# DS153-1_0-B.net
KiCad netlist of a schematic drawn in Altium Designer
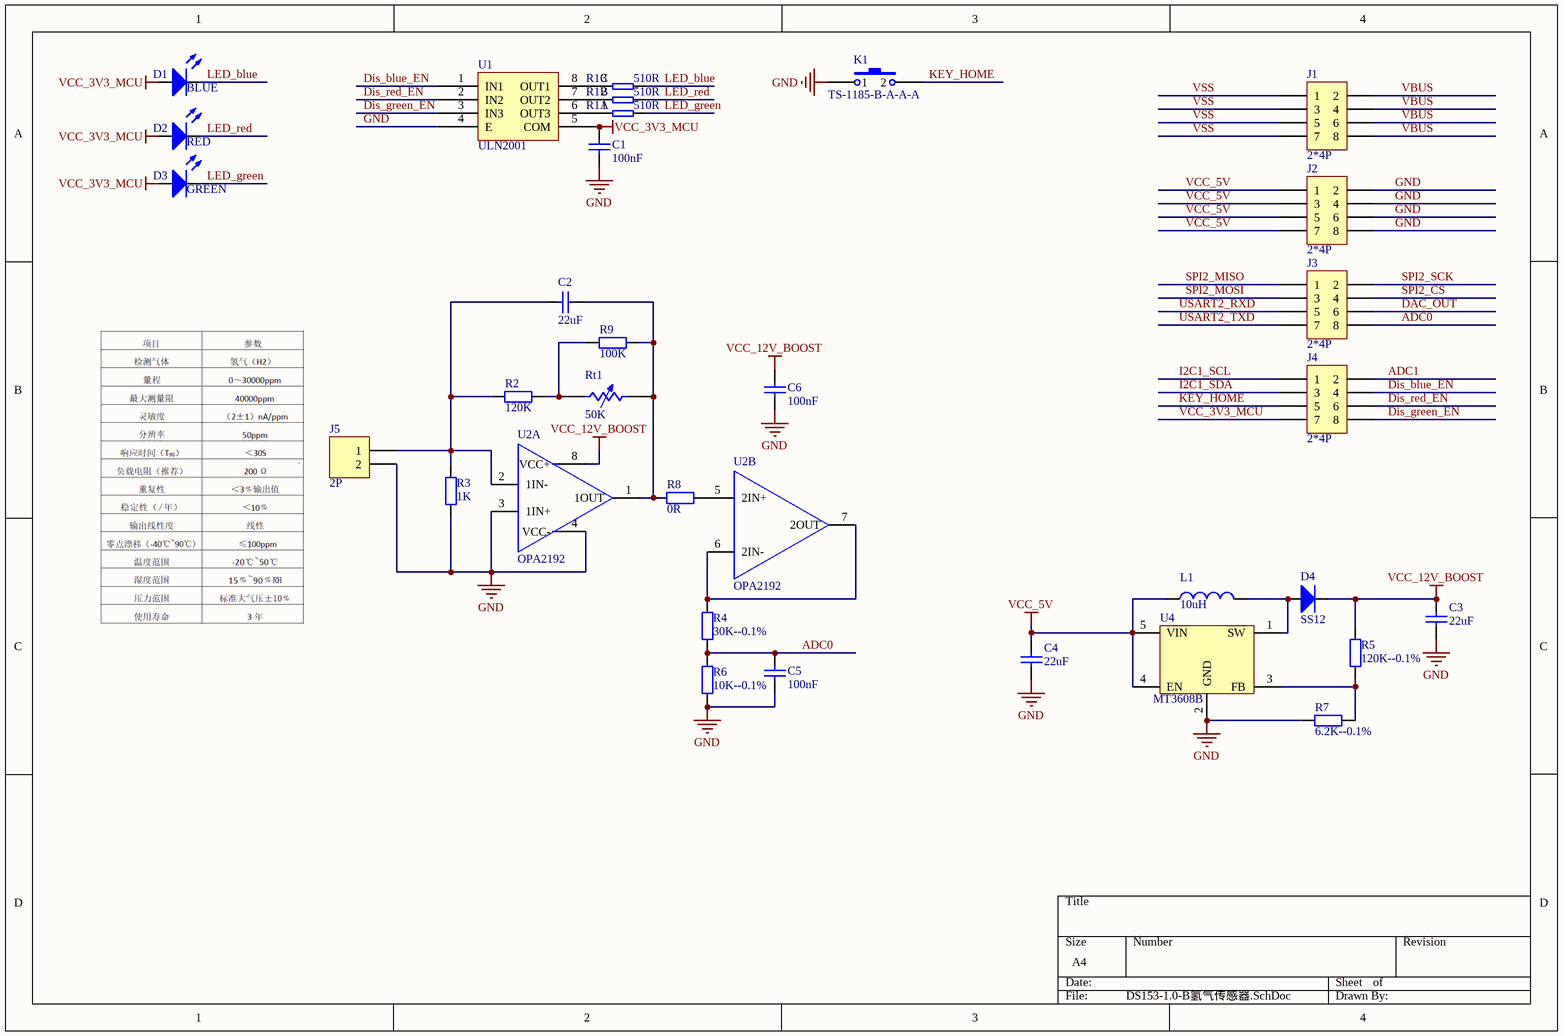
[diagram p0: DS153-1.0-B氢气传感器.SchDoc]

(export (version "E")
  (design (tool "Eeschema 10.0.6"))
  (components
    (comp (ref "C1")
      (value "100nF")
      (footprint "0603CAP")
      (description "贴片电容")
      (fields (field (name "Comment") "SMDCAP00013"))
      (libsource (lib "AD_SCH") (part "MLCC 100nF 50V ±10％ 0603"))
    )
    (comp (ref "C2")
      (value "22uF")
      (footprint "1206CAP")
      (description "贴片电容")
      (fields (field (name "Comment") "MLCC 22uF 50V ±20％ 1206"))
      (libsource (lib "AD_SCH") (part "MLCC 22uF 50V ±20％ 1206"))
    )
    (comp (ref "C3")
      (value "22uF")
      (footprint "1206CAP")
      (description "贴片电容")
      (fields (field (name "Comment") "MLCC 22uF 50V ±20％ 1206"))
      (libsource (lib "AD_SCH") (part "MLCC 22uF 50V ±20％ 1206"))
    )
    (comp (ref "C4")
      (value "22uF")
      (footprint "1206CAP")
      (description "贴片电容")
      (fields (field (name "Comment") "MLCC 22uF 50V ±20％ 1206"))
      (libsource (lib "AD_SCH") (part "MLCC 22uF 50V ±20％ 1206"))
    )
    (comp (ref "C5")
      (value "100nF")
      (footprint "0603CAP")
      (description "贴片电容")
      (fields (field (name "Comment") "SMDCAP00013"))
      (libsource (lib "AD_SCH") (part "MLCC 100nF 50V ±10％ 0603"))
    )
    (comp (ref "C6")
      (value "100nF")
      (footprint "0603CAP")
      (description "贴片电容")
      (fields (field (name "Comment") "SMDCAP00013"))
      (libsource (lib "AD_SCH") (part "MLCC 100nF 50V ±10％ 0603"))
    )
    (comp (ref "D1")
      (value "BLUE")
      (footprint "LED_0805")
      (description "贴片LED")
      (fields (field (name "Comment") "SMDLED00010"))
      (libsource (lib "AD_SCH") (part "Chip 蓝色LED 0805"))
    )
    (comp (ref "D2")
      (value "RED")
      (footprint "LED_0805")
      (description "贴片LED")
      (fields (field (name "Comment") "SMDLED00003"))
      (libsource (lib "AD_SCH") (part "Chip 红色LED 0805"))
    )
    (comp (ref "D3")
      (value "GREEN")
      (footprint "LED_0805")
      (description "贴片LED")
      (fields (field (name "Comment") "Chip 翠绿LED 0805"))
      (libsource (lib "AD_SCH") (part "Chip 翠绿LED 0805"))
    )
    (comp (ref "D4")
      (value "SS12")
      (footprint "SMA/DO-214AC")
      (description "贴片肖特基二极管")
      (fields (field (name "Comment") "SMDDIODE06003"))
      (libsource (lib "AD_SCH") (part "SS12 SMA/DO-214AC（1N5817）"))
    )
    (comp (ref "J1")
      (value "2*4P")
      (footprint "X1321WVS-2x04J-C40D53")
      (description "双排针2x4P 立贴 1.27mm")
      (fields (field (name "Comment") "X1321WVS-2x04J-C40D53"))
      (libsource (lib "AD_SCH") (part "X1321WVS-2x04J-C40D53"))
    )
    (comp (ref "J2")
      (value "2*4P")
      (footprint "X1321WVS-2x04J-C40D53")
      (description "双排针2x4P 立贴 1.27mm")
      (fields (field (name "Comment") "X1321WVS-2x04J-C40D53"))
      (libsource (lib "AD_SCH") (part "X1321WVS-2x04J-C40D53"))
    )
    (comp (ref "J3")
      (value "2*4P")
      (footprint "X1321WVS-2x04J-C40D53")
      (description "双排针2x4P 立贴 1.27mm")
      (fields (field (name "Comment") "X1321WVS-2x04J-C40D53"))
      (libsource (lib "AD_SCH") (part "X1321WVS-2x04J-C40D53"))
    )
    (comp (ref "J4")
      (value "2*4P")
      (footprint "X1321WVS-2x04J-C40D53")
      (description "双排针2x4P 立贴 1.27mm")
      (fields (field (name "Comment") "X1321WVS-2x04J-C40D53"))
      (libsource (lib "AD_SCH") (part "X1321WVS-2x04J-C40D53"))
    )
    (comp (ref "J5")
      (value "2P")
      (footprint "SIP2")
      (description "单排直针")
      (fields (field (name "Comment") "SL000000042"))
      (libsource (lib "AD_SCH") (part "DIP2 单排直针 1*40P 间距2.54mm 针长11mm 铜"))
    )
    (comp (ref "K1")
      (value "TS-1185-B-A-A-A")
      (footprint "KEY_TS-1185-x-A-A-A")
      (description "轻触开关")
      (libsource (lib "AD_SCH") (part "TS-1185-B-A-A-A"))
    )
    (comp (ref "L1")
      (value "小型化一体成型T-CORE,SMD,2x2.5mm")
      (footprint "SMD,2x2.5mm")
      (description "电感值 10uH ±20%\r\n饱和电流(Isat) 1.6A\r\n额定电流 1.2A\r\n直流电阻(DCR) 330mΩ")
      (libsource (lib "AD_SCH") (part "FTC252012S100MBCA"))
    )
    (comp (ref "R1")
      (value "510R")
      (footprint "0603RES_Pack4")
      (description "贴片排阻")
      (fields (field (name "Comment") "SMDRES05003"))
      (libsource (lib "AD_SCH") (part "Chip R*4 510R 1/16W ±5％ 0603"))
    )
    (comp (ref "R2")
      (value "120K")
      (footprint "0603RES")
      (description "贴片电阻")
      (fields (field (name "Comment") "Chip 120K 1/16W ±1％ 0603"))
      (libsource (lib "AD_SCH") (part "Chip 120K 1/16W ±1％ 0603"))
    )
    (comp (ref "R3")
      (value "1K")
      (footprint "0603RES")
      (description "贴片电阻")
      (fields (field (name "Comment") "SMDRES00034"))
      (libsource (lib "AD_SCH") (part "Chip 1K 1/16W ±1％ 0603"))
    )
    (comp (ref "R4")
      (value "30K--0.1%")
      (footprint "0603RES")
      (description "贴片电阻")
      (fields (field (name "Comment") "SMDRES00060"))
      (libsource (lib "AD_SCH") (part "Chip 30K 1/16W ±1％ 0603"))
    )
    (comp (ref "R5")
      (value "120K--0.1%")
      (footprint "0603RES")
      (description "贴片电阻")
      (fields (field (name "Comment") "Chip 120K 1/16W ±1％ 0603"))
      (libsource (lib "") (part "Chip 120K 1/16W ±1％ 0603_1"))
    )
    (comp (ref "R6")
      (value "10K--0.1%")
      (footprint "0603RES")
      (description "贴片电阻")
      (fields (field (name "Comment") "SMDRES00056"))
      (libsource (lib "AD_SCH") (part "Chip 10K 1/16W ±1％ 0603"))
    )
    (comp (ref "R7")
      (value "6.2K--0.1%")
      (footprint "0603RES")
      (description "贴片电阻")
      (fields (field (name "Comment") "SMDRES00056"))
      (libsource (lib "") (part "Chip 10K 1/16W ±1％ 0603_1"))
    )
    (comp (ref "R8")
      (value "0R")
      (footprint "0603RES")
      (description "贴片电阻")
      (fields (field (name "Comment") "Chip 0R 1/16W ±1％ 0603"))
      (libsource (lib "AD_SCH") (part "Chip 0R 1/16W ±1％ 0603"))
    )
    (comp (ref "R9")
      (value "100K")
      (footprint "0603RES")
      (description "贴片电阻")
      (fields (field (name "Comment") "SMDRES00071"))
      (libsource (lib "AD_SCH") (part "Chip 100K 1/16W ±1％ 0603"))
    )
    (comp (ref "Rt1")
      (value "50K")
      (footprint "DIP_CAP_2.54mm")
      (description "热敏电阻")
      (fields (field (name "Comment") "SE000000015"))
      (libsource (lib "AD_SCH") (part "NTC 10K 热敏电阻 5% Φ5 MF52A1 B值{colon}3950K"))
    )
    (comp (ref "U1")
      (value "ULN2001")
      (footprint "SO-8")
      (description "电机驱动芯片")
      (fields (field (name "Comment") "SMDIC000018"))
      (libsource (lib "AD_SCH") (part "ULN2001 SOP-8"))
    )
    (comp (ref "U2") (value "OPA2192") (footprint "SO-8") (libsource (lib "AD_SCH") (part "TL062C")))
    (comp (ref "U4")
      (value "MT3608B")
      (footprint "SOT23-6")
      (description "MT3608B 是一款高效的1.2MHz固定频率电流模式升压转换器。")
      (libsource (lib "AD_SCH") (part "MT3608B"))
    )
  )
  (nets
    (net (code "1") (name "/ADC0") (class "Default")
      (node (ref "C5") (pin "2") (pinfunction "2_2") (pintype "passive"))
      (node (ref "J3") (pin "8") (pinfunction "8_8") (pintype "passive"))
      (node (ref "R4") (pin "1") (pinfunction "1_1") (pintype "passive"))
      (node (ref "R6") (pin "2") (pinfunction "2_2") (pintype "passive"))
    )
    (net (code "2") (name "/ADC1") (class "Default")
      (node (ref "J4") (pin "2") (pinfunction "2_2") (pintype "passive"))
    )
    (net (code "3") (name "/DAC_OUT") (class "Default")
      (node (ref "J3") (pin "6") (pinfunction "6_6") (pintype "passive"))
    )
    (net (code "4") (name "/Dis_blue_EN") (class "Default")
      (node (ref "J4") (pin "4") (pinfunction "4_4") (pintype "passive"))
      (node (ref "U1") (pin "1") (pinfunction "IN1_1") (pintype "passive"))
    )
    (net (code "5") (name "/Dis_green_EN") (class "Default")
      (node (ref "J4") (pin "8") (pinfunction "8_8") (pintype "passive"))
      (node (ref "U1") (pin "3") (pinfunction "IN3_3") (pintype "passive"))
    )
    (net (code "6") (name "/Dis_red_EN") (class "Default")
      (node (ref "J4") (pin "6") (pinfunction "6_6") (pintype "passive"))
      (node (ref "U1") (pin "2") (pinfunction "IN2_2") (pintype "passive"))
    )
    (net (code "7") (name "/I2C1_SCL") (class "Default")
      (node (ref "J4") (pin "1") (pinfunction "1_1") (pintype "passive"))
    )
    (net (code "8") (name "/I2C1_SDA") (class "Default")
      (node (ref "J4") (pin "3") (pinfunction "3_3") (pintype "passive"))
    )
    (net (code "9") (name "/KEY_HOME") (class "Default")
      (node (ref "J4") (pin "5") (pinfunction "5_5") (pintype "passive"))
      (node (ref "K1") (pin "2") (pinfunction "2_2") (pintype "passive"))
    )
    (net (code "10") (name "/LED_blue") (class "Default")
      (node (ref "D1") (pin "2") (pinfunction "K_2") (pintype "passive"))
      (node (ref "R1") (pin "6") (pinfunction "6_6") (pintype "passive"))
    )
    (net (code "11") (name "/LED_green") (class "Default")
      (node (ref "D3") (pin "2") (pinfunction "K_2") (pintype "passive"))
      (node (ref "R1") (pin "8") (pinfunction "8_8") (pintype "passive"))
    )
    (net (code "12") (name "/LED_red") (class "Default")
      (node (ref "D2") (pin "2") (pinfunction "K_2") (pintype "passive"))
      (node (ref "R1") (pin "7") (pinfunction "7_7") (pintype "passive"))
    )
    (net (code "13") (name "/SPI2_CS") (class "Default")
      (node (ref "J3") (pin "4") (pinfunction "4_4") (pintype "passive"))
    )
    (net (code "14") (name "/SPI2_MISO") (class "Default")
      (node (ref "J3") (pin "1") (pinfunction "1_1") (pintype "passive"))
    )
    (net (code "15") (name "/SPI2_MOSI") (class "Default")
      (node (ref "J3") (pin "3") (pinfunction "3_3") (pintype "passive"))
    )
    (net (code "16") (name "/SPI2_SCK") (class "Default")
      (node (ref "J3") (pin "2") (pinfunction "2_2") (pintype "passive"))
    )
    (net (code "17") (name "/USART2_RXD") (class "Default")
      (node (ref "J3") (pin "5") (pinfunction "5_5") (pintype "passive"))
    )
    (net (code "18") (name "/USART2_TXD") (class "Default")
      (node (ref "J3") (pin "7") (pinfunction "7_7") (pintype "passive"))
    )
    (net (code "19") (name "/VBUS") (class "Default")
      (node (ref "J1") (pin "2") (pinfunction "2_2") (pintype "passive"))
      (node (ref "J1") (pin "4") (pinfunction "4_4") (pintype "passive"))
      (node (ref "J1") (pin "6") (pinfunction "6_6") (pintype "passive"))
      (node (ref "J1") (pin "8") (pinfunction "8_8") (pintype "passive"))
    )
    (net (code "20") (name "/VSS") (class "Default")
      (node (ref "J1") (pin "1") (pinfunction "1_1") (pintype "passive"))
      (node (ref "J1") (pin "3") (pinfunction "3_3") (pintype "passive"))
      (node (ref "J1") (pin "5") (pinfunction "5_5") (pintype "passive"))
      (node (ref "J1") (pin "7") (pinfunction "7_7") (pintype "passive"))
    )
    (net (code "21") (name "GND") (class "Default")
      (node (ref "C1") (pin "1") (pinfunction "1_1") (pintype "passive"))
      (node (ref "C3") (pin "2") (pinfunction "2_2") (pintype "passive"))
      (node (ref "C4") (pin "2") (pinfunction "2_2") (pintype "passive"))
      (node (ref "C5") (pin "1") (pinfunction "1_1") (pintype "passive"))
      (node (ref "C6") (pin "1") (pinfunction "1_1") (pintype "passive"))
      (node (ref "J2") (pin "2") (pinfunction "2_2") (pintype "passive"))
      (node (ref "J2") (pin "4") (pinfunction "4_4") (pintype "passive"))
      (node (ref "J2") (pin "6") (pinfunction "6_6") (pintype "passive"))
      (node (ref "J2") (pin "8") (pinfunction "8_8") (pintype "passive"))
      (node (ref "J5") (pin "2") (pinfunction "2_2") (pintype "passive"))
      (node (ref "K1") (pin "1") (pinfunction "1_1") (pintype "passive"))
      (node (ref "R3") (pin "1") (pinfunction "1_1") (pintype "passive"))
      (node (ref "R6") (pin "1") (pinfunction "1_1") (pintype "passive"))
      (node (ref "R7") (pin "1") (pinfunction "1_1") (pintype "passive"))
      (node (ref "U1") (pin "4") (pinfunction "E_4") (pintype "passive"))
      (node (ref "U2") (pin "3") (pinfunction "1IN+_3") (pintype "passive"))
      (node (ref "U2") (pin "4") (pinfunction "VCC-_4") (pintype "passive"))
      (node (ref "U4") (pin "2") (pinfunction "GND_2") (pintype "passive"))
    )
    (net (code "22") (name "Net-(D4-A)") (class "Default")
      (node (ref "D4") (pin "1") (pinfunction "A_1") (pintype "passive"))
      (node (ref "L1") (pin "2") (pinfunction "2_2") (pintype "passive"))
      (node (ref "U4") (pin "1") (pinfunction "SW_1") (pintype "passive"))
    )
    (net (code "23") (name "Net-(R2-Pad2)") (class "Default")
      (node (ref "R2") (pin "2") (pinfunction "2_2") (pintype "passive"))
      (node (ref "R9") (pin "1") (pinfunction "1_1") (pintype "passive"))
      (node (ref "Rt1") (pin "2") (pinfunction "2_2") (pintype "passive"))
    )
    (net (code "24") (name "Net-(U1-OUT1)") (class "Default")
      (node (ref "R1") (pin "3") (pinfunction "3_3") (pintype "passive"))
      (node (ref "U1") (pin "8") (pinfunction "OUT1_8") (pintype "passive"))
    )
    (net (code "25") (name "Net-(U1-OUT2)") (class "Default")
      (node (ref "R1") (pin "2") (pinfunction "2_2") (pintype "passive"))
      (node (ref "U1") (pin "7") (pinfunction "OUT2_7") (pintype "passive"))
    )
    (net (code "26") (name "Net-(U1-OUT3)") (class "Default")
      (node (ref "R1") (pin "1") (pinfunction "1_1") (pintype "passive"))
      (node (ref "U1") (pin "6") (pinfunction "OUT3_6") (pintype "passive"))
    )
    (net (code "27") (name "Net-(U2A-1IN-)") (class "Default")
      (node (ref "C2") (pin "1") (pinfunction "1_1") (pintype "passive"))
      (node (ref "J5") (pin "1") (pinfunction "1_1") (pintype "passive"))
      (node (ref "R2") (pin "1") (pinfunction "1_1") (pintype "passive"))
      (node (ref "R3") (pin "2") (pinfunction "2_2") (pintype "passive"))
      (node (ref "U2") (pin "2") (pinfunction "1IN-_2") (pintype "passive"))
    )
    (net (code "28") (name "Net-(U2A-1OUT)") (class "Default")
      (node (ref "C2") (pin "2") (pinfunction "2_2") (pintype "passive"))
      (node (ref "R8") (pin "1") (pinfunction "1_1") (pintype "passive"))
      (node (ref "R9") (pin "2") (pinfunction "2_2") (pintype "passive"))
      (node (ref "Rt1") (pin "1") (pinfunction "1_1") (pintype "passive"))
      (node (ref "U2") (pin "1") (pinfunction "1OUT_1") (pintype "passive"))
    )
    (net (code "29") (name "Net-(U2B-2IN+)") (class "Default")
      (node (ref "R8") (pin "2") (pinfunction "2_2") (pintype "passive"))
      (node (ref "U2") (pin "5") (pinfunction "2IN+_5") (pintype "passive"))
    )
    (net (code "30") (name "Net-(U2B-2IN-)") (class "Default")
      (node (ref "R4") (pin "2") (pinfunction "2_2") (pintype "passive"))
      (node (ref "U2") (pin "6") (pinfunction "2IN-_6") (pintype "passive"))
      (node (ref "U2") (pin "7") (pinfunction "2OUT_7") (pintype "passive"))
    )
    (net (code "31") (name "Net-(U4-FB)") (class "Default")
      (node (ref "R5") (pin "1") (pinfunction "1_1") (pintype "passive"))
      (node (ref "R7") (pin "2") (pinfunction "2_2") (pintype "passive"))
      (node (ref "U4") (pin "3") (pinfunction "FB_3") (pintype "passive"))
    )
    (net (code "32") (name "VCC_3V3_MCU") (class "Default")
      (node (ref "C1") (pin "2") (pinfunction "2_2") (pintype "passive"))
      (node (ref "D1") (pin "1") (pinfunction "A_1") (pintype "passive"))
      (node (ref "D2") (pin "1") (pinfunction "A_1") (pintype "passive"))
      (node (ref "D3") (pin "1") (pinfunction "A_1") (pintype "passive"))
      (node (ref "J4") (pin "7") (pinfunction "7_7") (pintype "passive"))
      (node (ref "U1") (pin "5") (pinfunction "COM_5") (pintype "passive"))
    )
    (net (code "33") (name "VCC_5V") (class "Default")
      (node (ref "C4") (pin "1") (pinfunction "1_1") (pintype "passive"))
      (node (ref "J2") (pin "1") (pinfunction "1_1") (pintype "passive"))
      (node (ref "J2") (pin "3") (pinfunction "3_3") (pintype "passive"))
      (node (ref "J2") (pin "5") (pinfunction "5_5") (pintype "passive"))
      (node (ref "J2") (pin "7") (pinfunction "7_7") (pintype "passive"))
      (node (ref "L1") (pin "1") (pinfunction "1_1") (pintype "passive"))
      (node (ref "U4") (pin "4") (pinfunction "EN_4") (pintype "passive"))
      (node (ref "U4") (pin "5") (pinfunction "VIN_5") (pintype "passive"))
    )
    (net (code "34") (name "VCC_12V_BOOST") (class "Default")
      (node (ref "C3") (pin "1") (pinfunction "1_1") (pintype "passive"))
      (node (ref "C6") (pin "2") (pinfunction "2_2") (pintype "passive"))
      (node (ref "D4") (pin "2") (pinfunction "K_2") (pintype "passive"))
      (node (ref "R5") (pin "2") (pinfunction "2_2") (pintype "passive"))
      (node (ref "U2") (pin "8") (pinfunction "VCC+_8") (pintype "passive"))
    )
    (net (code "35") (name "unconnected-(U4-NC-Pad6)") (class "Default")
      (node (ref "U4") (pin "6") (pinfunction "NC_6") (pintype "passive"))
    )
  )
)
